# My4G.net
KiCad netlist of a schematic drawn in Altium Designer
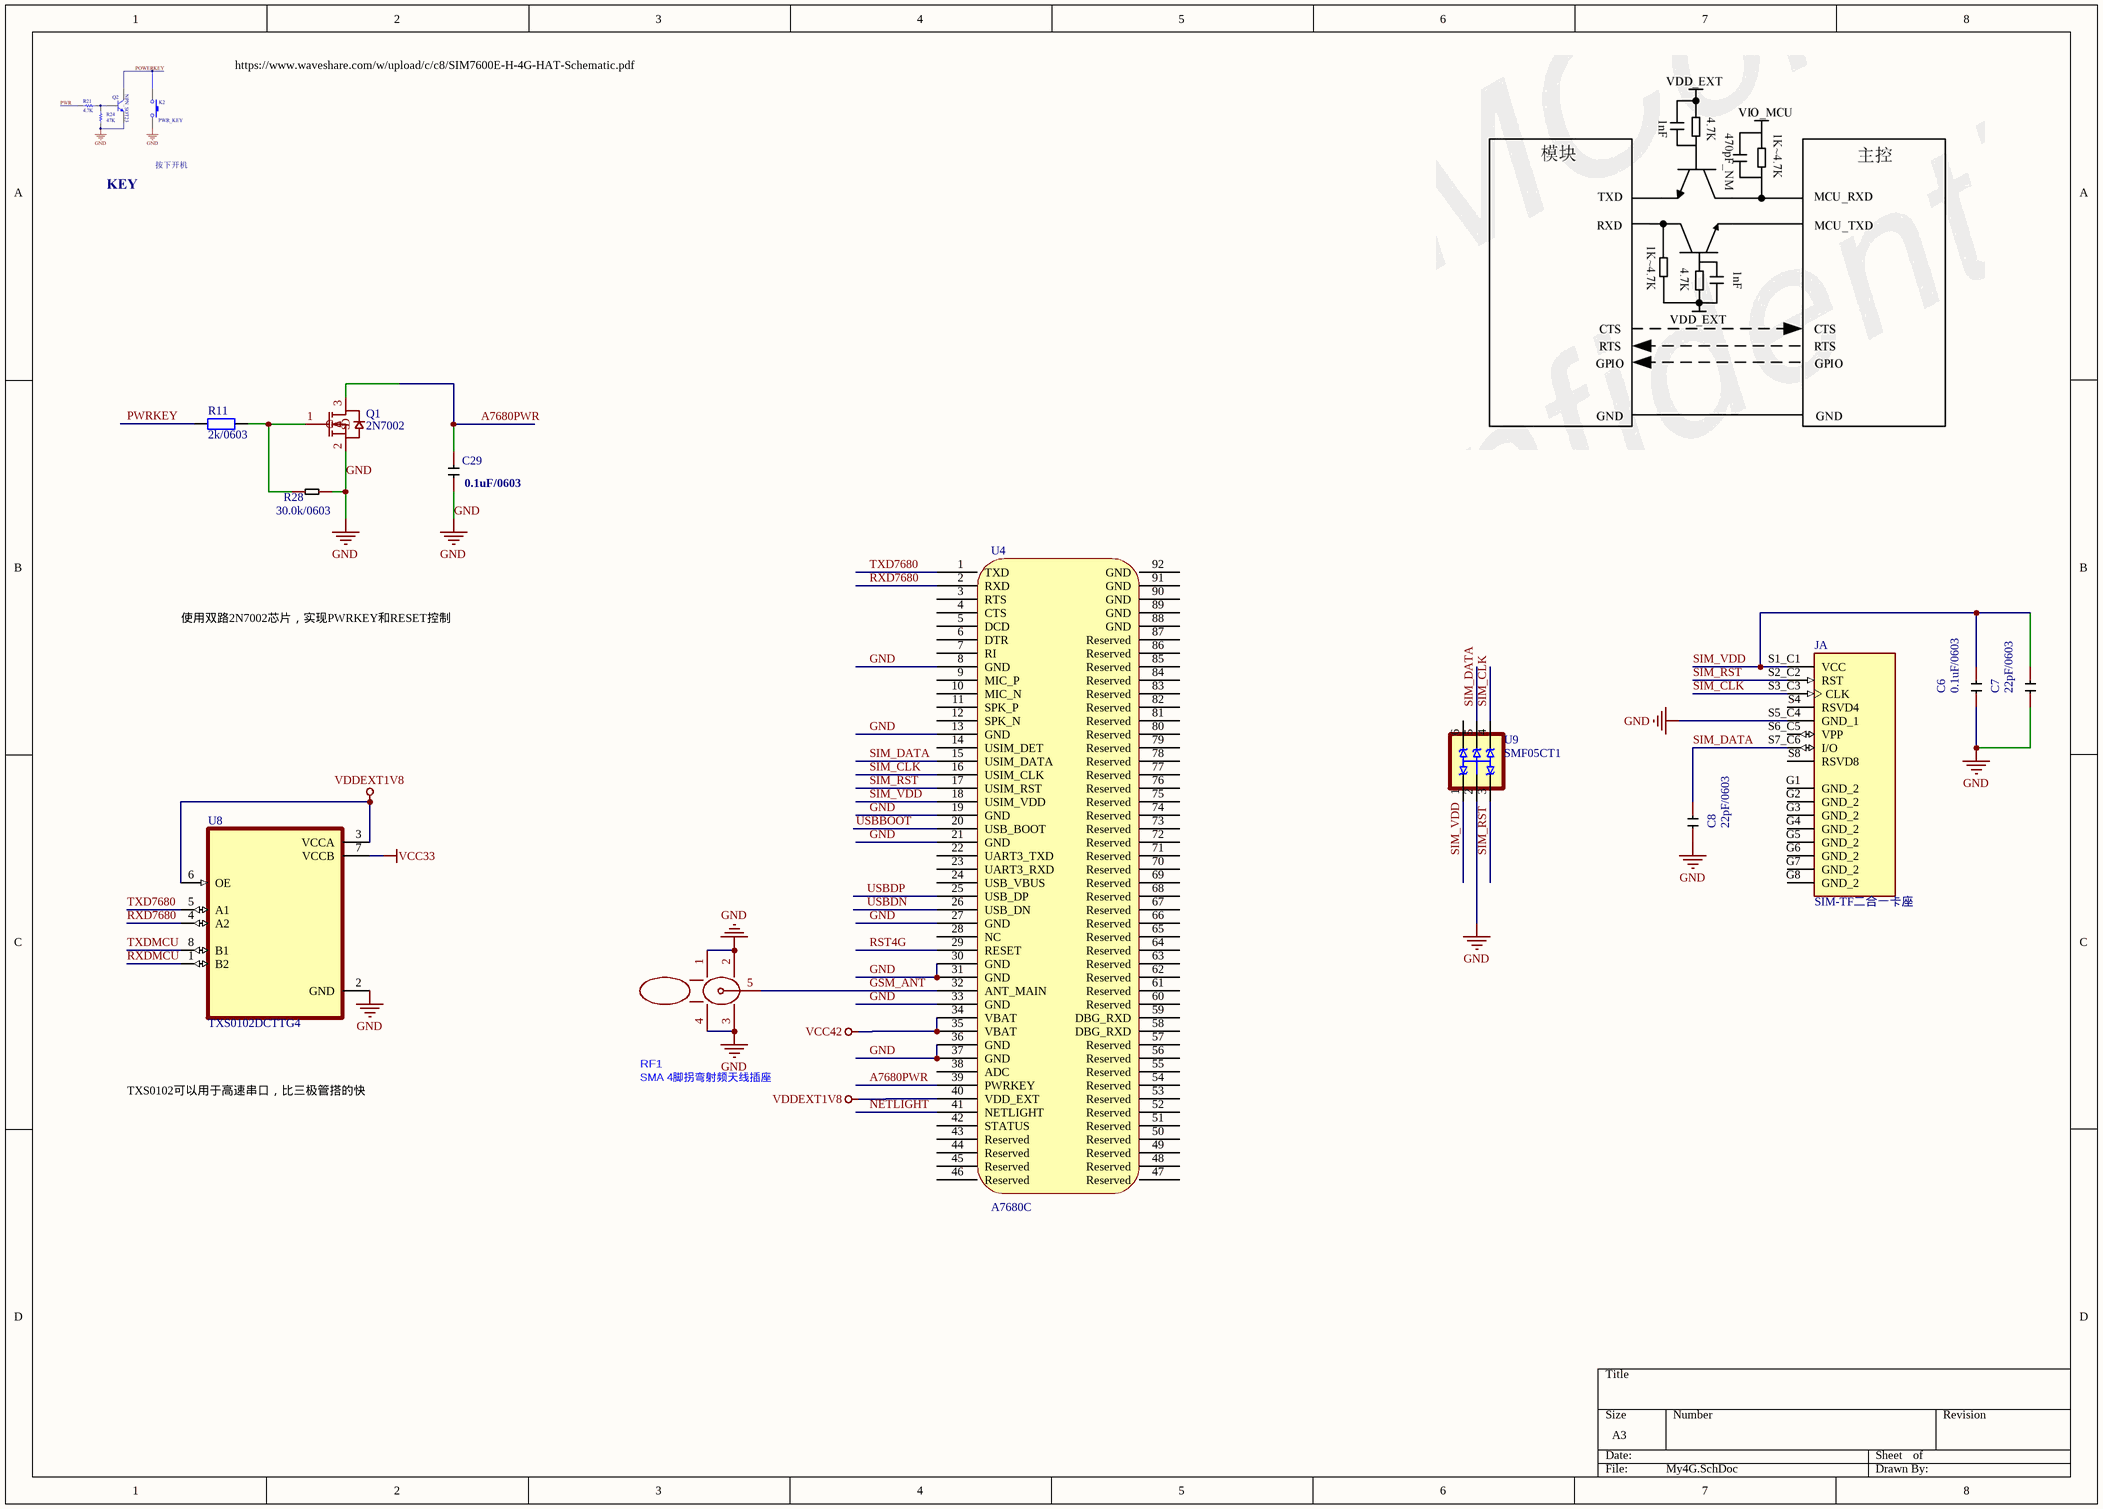
[diagram p0: My4G.SchDoc]

(export (version "E")
  (design (tool "Eeschema 10.0.6"))
  (components
    (comp (ref "C6")
      (value "0.1uF/0603")
      (footprint "CAP0603")
      (libsource (lib "altium-import") (part "root_1_Discrete_C*_-0603_"))
    )
    (comp (ref "C7")
      (value "22pF/0603")
      (footprint "CAP0603")
      (libsource (lib "altium-import") (part "root_1_Discrete_C*_-0603_"))
    )
    (comp (ref "C8")
      (value "22pF/0603")
      (footprint "CAP0603")
      (libsource (lib "altium-import") (part "root_1_Discrete_C*_-0603_"))
    )
    (comp (ref "C29")
      (value "0.1uF/0603")
      (footprint "CAP0603")
      (libsource (lib "altium-import") (part "root_1_Discrete_C*_-0603_"))
    )
    (comp (ref "J")
      (value "SIM-TF二合一卡座")
      (footprint "MOLEX_104642-1610")
      (fields (field (name "MF") "Molex") (field (name "MP") "104642-1610"))
      (libsource (lib "ESPC6IOTALLinOne") (part "104642-1610"))
    )
    (comp (ref "Q1")
      (value "2N7002")
      (footprint "SOT-23_2N7002")
      (description "Nmos 2N7000, 2N7002, NDS7002A")
      (libsource (lib "ChargingPile") (part "2N7002"))
    )
    (comp (ref "R11")
      (value "2k/0603")
      (footprint "RES0603")
      (fields (field (name "PUBLISHER") "Altium Limited"))
      (libsource (lib "Miscellaneous Devices") (part "Res2"))
    )
    (comp (ref "R28")
      (value "30.0k/0603")
      (footprint "RES0603")
      (libsource (lib "altium-import") (part "root_0_mirrored_Discrete_R*_-0603_"))
    )
    (comp (ref "RF1")
      (value "SMA 4脚拐弯射频天线插座")
      (footprint "SMA-TH_BWSMA-KWE-Z001")
      (libsource (lib "altium-import") (part "root_1_BWSMA-KWE-Z001_"))
    )
    (comp (ref "U4")
      (value "A7680C")
      (footprint "LCC-LAG_L17.6-W15.7_A7680C")
      (description "4G cat1 module")
      (libsource (lib "altium-import") (part "root_0_A7680C-LAAS_"))
    )
    (comp (ref "U8")
      (value "TXS0102DCTTG4")
      (footprint "TXS0102")
      (description "2-Bit Bidirectional Voltage-Level Shifter for Open-Drain and Push-Pull Application 8-SM8 -40 to 85")
      (fields (field (name "MF") "Texas Instruments"))
      (libsource (lib "mySCH") (part "TXS0102DCTTG4"))
    )
    (comp (ref "U9")
      (value "SMF05CT1")
      (footprint "SMF05C-SC706")
      (description "12.5V Clamp 8A (8/20Âµs) Ipp Tvs Diode Surface Mount SC-88/SC70-6/SOT-363")
      (fields (field (name "MF") "ON Semiconductor"))
      (libsource (lib "mySCH") (part "SMF05CT1"))
    )
  )
  (nets
    (net (code "1") (name "/A7680PWR") (class "Default")
      (node (ref "C29") (pin "2") (pinfunction "2_2") (pintype "passive"))
      (node (ref "Q1") (pin "3") (pinfunction "D_3") (pintype "passive"))
      (node (ref "U4") (pin "39") (pinfunction "PWRKEY_39") (pintype "passive"))
    )
    (net (code "2") (name "/GSM_ANT") (class "Default")
      (node (ref "RF1") (pin "5") (pinfunction "5_5") (pintype "passive"))
      (node (ref "U4") (pin "32") (pinfunction "ANT_MAIN_32") (pintype "passive"))
    )
    (net (code "3") (name "/NETLIGHT") (class "Default")
      (node (ref "U4") (pin "41") (pinfunction "NETLIGHT_41") (pintype "passive"))
    )
    (net (code "4") (name "/PWRKEY") (class "Default")
      (node (ref "R11") (pin "1") (pinfunction "1_1") (pintype "passive"))
    )
    (net (code "5") (name "/RST4G") (class "Default")
      (node (ref "U4") (pin "29") (pinfunction "RESET_29") (pintype "passive"))
    )
    (net (code "6") (name "/RXD7680") (class "Default")
      (node (ref "U4") (pin "2") (pinfunction "RXD_2") (pintype "passive"))
      (node (ref "U8") (pin "4") (pinfunction "A2_4") (pintype "bidirectional"))
    )
    (net (code "7") (name "/RXDMCU") (class "Default")
      (node (ref "U8") (pin "1") (pinfunction "B2_1") (pintype "bidirectional"))
    )
    (net (code "8") (name "/SIM_CLK") (class "Default")
      (node (ref "J") (pin "S3_C3") (pinfunction "CLK_S3_C3") (pintype "input"))
      (node (ref "U4") (pin "16") (pinfunction "USIM_CLK_16") (pintype "passive"))
      (node (ref "U9") (pin "4") (pinfunction "C3_4") (pintype "passive"))
    )
    (net (code "9") (name "/SIM_DATA") (class "Default")
      (node (ref "C8") (pin "2") (pinfunction "2_2") (pintype "passive"))
      (node (ref "J") (pin "S7_C6") (pinfunction "I/O_S7_C6") (pintype "bidirectional"))
      (node (ref "U4") (pin "15") (pinfunction "USIM_DATA_15") (pintype "passive"))
      (node (ref "U9") (pin "5") (pinfunction "C4_5") (pintype "passive"))
    )
    (net (code "10") (name "/SIM_RST") (class "Default")
      (node (ref "J") (pin "S2_C2") (pinfunction "RST_S2_C2") (pintype "input"))
      (node (ref "U4") (pin "17") (pinfunction "USIM_RST_17") (pintype "passive"))
      (node (ref "U9") (pin "3") (pinfunction "C2_3") (pintype "passive"))
    )
    (net (code "11") (name "/SIM_VDD") (class "Default")
      (node (ref "C6") (pin "2") (pinfunction "2_2") (pintype "passive"))
      (node (ref "C7") (pin "2") (pinfunction "2_2") (pintype "passive"))
      (node (ref "J") (pin "S1_C1") (pinfunction "VCC_S1_C1") (pintype "power_in"))
      (node (ref "U4") (pin "18") (pinfunction "USIM_VDD_18") (pintype "passive"))
      (node (ref "U9") (pin "1") (pinfunction "C1_1") (pintype "passive"))
    )
    (net (code "12") (name "/TXD7680") (class "Default")
      (node (ref "U4") (pin "1") (pinfunction "TXD_1") (pintype "passive"))
      (node (ref "U8") (pin "5") (pinfunction "A1_5") (pintype "bidirectional"))
    )
    (net (code "13") (name "/TXDMCU") (class "Default")
      (node (ref "U8") (pin "8") (pinfunction "B1_8") (pintype "bidirectional"))
    )
    (net (code "14") (name "/USBBOOT") (class "Default")
      (node (ref "U4") (pin "20") (pinfunction "USB_BOOT_20") (pintype "passive"))
    )
    (net (code "15") (name "/USBDN") (class "Default")
      (node (ref "U4") (pin "26") (pinfunction "USB_DN_26") (pintype "passive"))
    )
    (net (code "16") (name "/USBDP") (class "Default")
      (node (ref "U4") (pin "25") (pinfunction "USB_DP_25") (pintype "passive"))
    )
    (net (code "17") (name "GND") (class "Default")
      (node (ref "C29") (pin "1") (pinfunction "1_1") (pintype "passive"))
      (node (ref "C6") (pin "1") (pinfunction "1_1") (pintype "passive"))
      (node (ref "C7") (pin "1") (pinfunction "1_1") (pintype "passive"))
      (node (ref "C8") (pin "1") (pinfunction "1_1") (pintype "passive"))
      (node (ref "J") (pin "S5_C4") (pinfunction "GND_1_S5_C4") (pintype "power_in"))
      (node (ref "Q1") (pin "2") (pinfunction "S_2") (pintype "passive"))
      (node (ref "R28") (pin "1") (pinfunction "1_1") (pintype "passive"))
      (node (ref "RF1") (pin "1") (pinfunction "1_1") (pintype "passive"))
      (node (ref "RF1") (pin "2") (pinfunction "2_2") (pintype "passive"))
      (node (ref "RF1") (pin "3") (pinfunction "3_3") (pintype "passive"))
      (node (ref "RF1") (pin "4") (pinfunction "4_4") (pintype "passive"))
      (node (ref "U4") (pin "13") (pinfunction "GND_13") (pintype "passive"))
      (node (ref "U4") (pin "19") (pinfunction "GND_19") (pintype "passive"))
      (node (ref "U4") (pin "21") (pinfunction "GND_21") (pintype "passive"))
      (node (ref "U4") (pin "27") (pinfunction "GND_27") (pintype "passive"))
      (node (ref "U4") (pin "30") (pinfunction "GND_30") (pintype "passive"))
      (node (ref "U4") (pin "31") (pinfunction "GND_31") (pintype "passive"))
      (node (ref "U4") (pin "33") (pinfunction "GND_33") (pintype "passive"))
      (node (ref "U4") (pin "36") (pinfunction "GND_36") (pintype "passive"))
      (node (ref "U4") (pin "37") (pinfunction "GND_37") (pintype "passive"))
      (node (ref "U4") (pin "8") (pinfunction "GND_8") (pintype "passive"))
      (node (ref "U8") (pin "2") (pinfunction "GND_2") (pintype "power_in"))
      (node (ref "U9") (pin "2") (pinfunction "A_2") (pintype "passive"))
    )
    (net (code "18") (name "Net-(Q1-G)") (class "Default")
      (node (ref "Q1") (pin "1") (pinfunction "G_1") (pintype "passive"))
      (node (ref "R11") (pin "2") (pinfunction "2_2") (pintype "passive"))
      (node (ref "R28") (pin "2") (pinfunction "2_2") (pintype "passive"))
    )
    (net (code "19") (name "VCC33") (class "Default")
      (node (ref "U8") (pin "7") (pinfunction "VCCB_7") (pintype "power_in"))
    )
    (net (code "20") (name "VCC42") (class "Default")
      (node (ref "U4") (pin "34") (pinfunction "VBAT_34") (pintype "passive"))
      (node (ref "U4") (pin "35") (pinfunction "VBAT_35") (pintype "passive"))
    )
    (net (code "21") (name "VDDEXT1V8") (class "Default")
      (node (ref "U4") (pin "40") (pinfunction "VDD_EXT_40") (pintype "passive"))
      (node (ref "U8") (pin "3") (pinfunction "VCCA_3") (pintype "power_in"))
      (node (ref "U8") (pin "6") (pinfunction "OE_6") (pintype "input"))
    )
    (net (code "22") (name "unconnected-(JA-GND_2-PadG1)") (class "Default")
      (node (ref "J") (pin "G1") (pinfunction "GND_2_G1") (pintype "power_in"))
    )
    (net (code "23") (name "unconnected-(JA-GND_2-PadG2)") (class "Default")
      (node (ref "J") (pin "G2") (pinfunction "GND_2_G2") (pintype "power_in"))
    )
    (net (code "24") (name "unconnected-(JA-GND_2-PadG3)") (class "Default")
      (node (ref "J") (pin "G3") (pinfunction "GND_2_G3") (pintype "power_in"))
    )
    (net (code "25") (name "unconnected-(JA-GND_2-PadG4)") (class "Default")
      (node (ref "J") (pin "G4") (pinfunction "GND_2_G4") (pintype "power_in"))
    )
    (net (code "26") (name "unconnected-(JA-GND_2-PadG5)") (class "Default")
      (node (ref "J") (pin "G5") (pinfunction "GND_2_G5") (pintype "power_in"))
    )
    (net (code "27") (name "unconnected-(JA-GND_2-PadG6)") (class "Default")
      (node (ref "J") (pin "G6") (pinfunction "GND_2_G6") (pintype "power_in"))
    )
    (net (code "28") (name "unconnected-(JA-GND_2-PadG7)") (class "Default")
      (node (ref "J") (pin "G7") (pinfunction "GND_2_G7") (pintype "power_in"))
    )
    (net (code "29") (name "unconnected-(JA-GND_2-PadG8)") (class "Default")
      (node (ref "J") (pin "G8") (pinfunction "GND_2_G8") (pintype "power_in"))
    )
    (net (code "30") (name "unconnected-(JA-RSVD4-PadS4)") (class "Default")
      (node (ref "J") (pin "S4") (pinfunction "RSVD4_S4") (pintype "passive"))
    )
    (net (code "31") (name "unconnected-(JA-RSVD8-PadS8)") (class "Default")
      (node (ref "J") (pin "S8") (pinfunction "RSVD8_S8") (pintype "passive"))
    )
    (net (code "32") (name "unconnected-(JA-VPP-PadS6_C5)") (class "Default")
      (node (ref "J") (pin "S6_C5") (pinfunction "VPP_S6_C5") (pintype "bidirectional"))
    )
    (net (code "33") (name "unconnected-(U4-ADC-Pad38)") (class "Default")
      (node (ref "U4") (pin "38") (pinfunction "ADC_38") (pintype "passive"))
    )
    (net (code "34") (name "unconnected-(U4-CTS-Pad4)") (class "Default")
      (node (ref "U4") (pin "4") (pinfunction "CTS_4") (pintype "passive"))
    )
    (net (code "35") (name "unconnected-(U4-DBG_RXD-Pad58)") (class "Default")
      (node (ref "U4") (pin "58") (pinfunction "DBG_RXD_58") (pintype "passive"))
    )
    (net (code "36") (name "unconnected-(U4-DBG_RXD-Pad59)") (class "Default")
      (node (ref "U4") (pin "59") (pinfunction "DBG_RXD_59") (pintype "passive"))
    )
    (net (code "37") (name "unconnected-(U4-DCD-Pad5)") (class "Default")
      (node (ref "U4") (pin "5") (pinfunction "DCD_5") (pintype "passive"))
    )
    (net (code "38") (name "unconnected-(U4-DTR-Pad6)") (class "Default")
      (node (ref "U4") (pin "6") (pinfunction "DTR_6") (pintype "passive"))
    )
    (net (code "39") (name "unconnected-(U4-GND-Pad88)") (class "Default")
      (node (ref "U4") (pin "88") (pinfunction "GND_88") (pintype "passive"))
    )
    (net (code "40") (name "unconnected-(U4-GND-Pad89)") (class "Default")
      (node (ref "U4") (pin "89") (pinfunction "GND_89") (pintype "passive"))
    )
    (net (code "41") (name "unconnected-(U4-GND-Pad90)") (class "Default")
      (node (ref "U4") (pin "90") (pinfunction "GND_90") (pintype "passive"))
    )
    (net (code "42") (name "unconnected-(U4-GND-Pad91)") (class "Default")
      (node (ref "U4") (pin "91") (pinfunction "GND_91") (pintype "passive"))
    )
    (net (code "43") (name "unconnected-(U4-GND-Pad92)") (class "Default")
      (node (ref "U4") (pin "92") (pinfunction "GND_92") (pintype "passive"))
    )
    (net (code "44") (name "unconnected-(U4-MIC_N-Pad10)") (class "Default")
      (node (ref "U4") (pin "10") (pinfunction "MIC_N_10") (pintype "passive"))
    )
    (net (code "45") (name "unconnected-(U4-MIC_P-Pad9)") (class "Default")
      (node (ref "U4") (pin "9") (pinfunction "MIC_P_9") (pintype "passive"))
    )
    (net (code "46") (name "unconnected-(U4-NC-Pad28)") (class "Default")
      (node (ref "U4") (pin "28") (pinfunction "NC_28") (pintype "passive"))
    )
    (net (code "47") (name "unconnected-(U4-RI-Pad7)") (class "Default")
      (node (ref "U4") (pin "7") (pinfunction "RI_7") (pintype "passive"))
    )
    (net (code "48") (name "unconnected-(U4-RTS-Pad3)") (class "Default")
      (node (ref "U4") (pin "3") (pinfunction "RTS_3") (pintype "passive"))
    )
    (net (code "49") (name "unconnected-(U4-Reserved-Pad43)") (class "Default")
      (node (ref "U4") (pin "43") (pinfunction "Reserved_43") (pintype "passive"))
    )
    (net (code "50") (name "unconnected-(U4-Reserved-Pad44)") (class "Default")
      (node (ref "U4") (pin "44") (pinfunction "Reserved_44") (pintype "passive"))
    )
    (net (code "51") (name "unconnected-(U4-Reserved-Pad45)") (class "Default")
      (node (ref "U4") (pin "45") (pinfunction "Reserved_45") (pintype "passive"))
    )
    (net (code "52") (name "unconnected-(U4-Reserved-Pad46)") (class "Default")
      (node (ref "U4") (pin "46") (pinfunction "Reserved_46") (pintype "passive"))
    )
    (net (code "53") (name "unconnected-(U4-Reserved-Pad47)") (class "Default")
      (node (ref "U4") (pin "47") (pinfunction "Reserved_47") (pintype "passive"))
    )
    (net (code "54") (name "unconnected-(U4-Reserved-Pad48)") (class "Default")
      (node (ref "U4") (pin "48") (pinfunction "Reserved_48") (pintype "passive"))
    )
    (net (code "55") (name "unconnected-(U4-Reserved-Pad49)") (class "Default")
      (node (ref "U4") (pin "49") (pinfunction "Reserved_49") (pintype "passive"))
    )
    (net (code "56") (name "unconnected-(U4-Reserved-Pad50)") (class "Default")
      (node (ref "U4") (pin "50") (pinfunction "Reserved_50") (pintype "passive"))
    )
    (net (code "57") (name "unconnected-(U4-Reserved-Pad51)") (class "Default")
      (node (ref "U4") (pin "51") (pinfunction "Reserved_51") (pintype "passive"))
    )
    (net (code "58") (name "unconnected-(U4-Reserved-Pad52)") (class "Default")
      (node (ref "U4") (pin "52") (pinfunction "Reserved_52") (pintype "passive"))
    )
    (net (code "59") (name "unconnected-(U4-Reserved-Pad53)") (class "Default")
      (node (ref "U4") (pin "53") (pinfunction "Reserved_53") (pintype "passive"))
    )
    (net (code "60") (name "unconnected-(U4-Reserved-Pad54)") (class "Default")
      (node (ref "U4") (pin "54") (pinfunction "Reserved_54") (pintype "passive"))
    )
    (net (code "61") (name "unconnected-(U4-Reserved-Pad55)") (class "Default")
      (node (ref "U4") (pin "55") (pinfunction "Reserved_55") (pintype "passive"))
    )
    (net (code "62") (name "unconnected-(U4-Reserved-Pad56)") (class "Default")
      (node (ref "U4") (pin "56") (pinfunction "Reserved_56") (pintype "passive"))
    )
    (net (code "63") (name "unconnected-(U4-Reserved-Pad57)") (class "Default")
      (node (ref "U4") (pin "57") (pinfunction "Reserved_57") (pintype "passive"))
    )
    (net (code "64") (name "unconnected-(U4-Reserved-Pad60)") (class "Default")
      (node (ref "U4") (pin "60") (pinfunction "Reserved_60") (pintype "passive"))
    )
    (net (code "65") (name "unconnected-(U4-Reserved-Pad61)") (class "Default")
      (node (ref "U4") (pin "61") (pinfunction "Reserved_61") (pintype "passive"))
    )
    (net (code "66") (name "unconnected-(U4-Reserved-Pad62)") (class "Default")
      (node (ref "U4") (pin "62") (pinfunction "Reserved_62") (pintype "passive"))
    )
    (net (code "67") (name "unconnected-(U4-Reserved-Pad63)") (class "Default")
      (node (ref "U4") (pin "63") (pinfunction "Reserved_63") (pintype "passive"))
    )
    (net (code "68") (name "unconnected-(U4-Reserved-Pad64)") (class "Default")
      (node (ref "U4") (pin "64") (pinfunction "Reserved_64") (pintype "passive"))
    )
    (net (code "69") (name "unconnected-(U4-Reserved-Pad65)") (class "Default")
      (node (ref "U4") (pin "65") (pinfunction "Reserved_65") (pintype "passive"))
    )
    (net (code "70") (name "unconnected-(U4-Reserved-Pad66)") (class "Default")
      (node (ref "U4") (pin "66") (pinfunction "Reserved_66") (pintype "passive"))
    )
    (net (code "71") (name "unconnected-(U4-Reserved-Pad67)") (class "Default")
      (node (ref "U4") (pin "67") (pinfunction "Reserved_67") (pintype "passive"))
    )
    (net (code "72") (name "unconnected-(U4-Reserved-Pad68)") (class "Default")
      (node (ref "U4") (pin "68") (pinfunction "Reserved_68") (pintype "passive"))
    )
    (net (code "73") (name "unconnected-(U4-Reserved-Pad69)") (class "Default")
      (node (ref "U4") (pin "69") (pinfunction "Reserved_69") (pintype "passive"))
    )
    (net (code "74") (name "unconnected-(U4-Reserved-Pad70)") (class "Default")
      (node (ref "U4") (pin "70") (pinfunction "Reserved_70") (pintype "passive"))
    )
    (net (code "75") (name "unconnected-(U4-Reserved-Pad71)") (class "Default")
      (node (ref "U4") (pin "71") (pinfunction "Reserved_71") (pintype "passive"))
    )
    (net (code "76") (name "unconnected-(U4-Reserved-Pad72)") (class "Default")
      (node (ref "U4") (pin "72") (pinfunction "Reserved_72") (pintype "passive"))
    )
    (net (code "77") (name "unconnected-(U4-Reserved-Pad73)") (class "Default")
      (node (ref "U4") (pin "73") (pinfunction "Reserved_73") (pintype "passive"))
    )
    (net (code "78") (name "unconnected-(U4-Reserved-Pad74)") (class "Default")
      (node (ref "U4") (pin "74") (pinfunction "Reserved_74") (pintype "passive"))
    )
    (net (code "79") (name "unconnected-(U4-Reserved-Pad75)") (class "Default")
      (node (ref "U4") (pin "75") (pinfunction "Reserved_75") (pintype "passive"))
    )
    (net (code "80") (name "unconnected-(U4-Reserved-Pad76)") (class "Default")
      (node (ref "U4") (pin "76") (pinfunction "Reserved_76") (pintype "passive"))
    )
    (net (code "81") (name "unconnected-(U4-Reserved-Pad77)") (class "Default")
      (node (ref "U4") (pin "77") (pinfunction "Reserved_77") (pintype "passive"))
    )
    (net (code "82") (name "unconnected-(U4-Reserved-Pad78)") (class "Default")
      (node (ref "U4") (pin "78") (pinfunction "Reserved_78") (pintype "passive"))
    )
    (net (code "83") (name "unconnected-(U4-Reserved-Pad79)") (class "Default")
      (node (ref "U4") (pin "79") (pinfunction "Reserved_79") (pintype "passive"))
    )
    (net (code "84") (name "unconnected-(U4-Reserved-Pad80)") (class "Default")
      (node (ref "U4") (pin "80") (pinfunction "Reserved_80") (pintype "passive"))
    )
    (net (code "85") (name "unconnected-(U4-Reserved-Pad81)") (class "Default")
      (node (ref "U4") (pin "81") (pinfunction "Reserved_81") (pintype "passive"))
    )
    (net (code "86") (name "unconnected-(U4-Reserved-Pad82)") (class "Default")
      (node (ref "U4") (pin "82") (pinfunction "Reserved_82") (pintype "passive"))
    )
    (net (code "87") (name "unconnected-(U4-Reserved-Pad83)") (class "Default")
      (node (ref "U4") (pin "83") (pinfunction "Reserved_83") (pintype "passive"))
    )
    (net (code "88") (name "unconnected-(U4-Reserved-Pad84)") (class "Default")
      (node (ref "U4") (pin "84") (pinfunction "Reserved_84") (pintype "passive"))
    )
    (net (code "89") (name "unconnected-(U4-Reserved-Pad85)") (class "Default")
      (node (ref "U4") (pin "85") (pinfunction "Reserved_85") (pintype "passive"))
    )
    (net (code "90") (name "unconnected-(U4-Reserved-Pad86)") (class "Default")
      (node (ref "U4") (pin "86") (pinfunction "Reserved_86") (pintype "passive"))
    )
    (net (code "91") (name "unconnected-(U4-Reserved-Pad87)") (class "Default")
      (node (ref "U4") (pin "87") (pinfunction "Reserved_87") (pintype "passive"))
    )
    (net (code "92") (name "unconnected-(U4-SPK_N-Pad12)") (class "Default")
      (node (ref "U4") (pin "12") (pinfunction "SPK_N_12") (pintype "passive"))
    )
    (net (code "93") (name "unconnected-(U4-SPK_P-Pad11)") (class "Default")
      (node (ref "U4") (pin "11") (pinfunction "SPK_P_11") (pintype "passive"))
    )
    (net (code "94") (name "unconnected-(U4-STATUS-Pad42)") (class "Default")
      (node (ref "U4") (pin "42") (pinfunction "STATUS_42") (pintype "passive"))
    )
    (net (code "95") (name "unconnected-(U4-UART3_RXD-Pad23)") (class "Default")
      (node (ref "U4") (pin "23") (pinfunction "UART3_RXD_23") (pintype "passive"))
    )
    (net (code "96") (name "unconnected-(U4-UART3_TXD-Pad22)") (class "Default")
      (node (ref "U4") (pin "22") (pinfunction "UART3_TXD_22") (pintype "passive"))
    )
    (net (code "97") (name "unconnected-(U4-USB_VBUS-Pad24)") (class "Default")
      (node (ref "U4") (pin "24") (pinfunction "USB_VBUS_24") (pintype "passive"))
    )
    (net (code "98") (name "unconnected-(U4-USIM_DET-Pad14)") (class "Default")
      (node (ref "U4") (pin "14") (pinfunction "USIM_DET_14") (pintype "passive"))
    )
    (net (code "99") (name "unconnected-(U9-C5-Pad6)") (class "Default")
      (node (ref "U9") (pin "6") (pinfunction "C5_6") (pintype "passive"))
    )
  )
)
